# Sheet_1_2022-03-15.net
KiCad netlist of a schematic drawn in Altium Designer
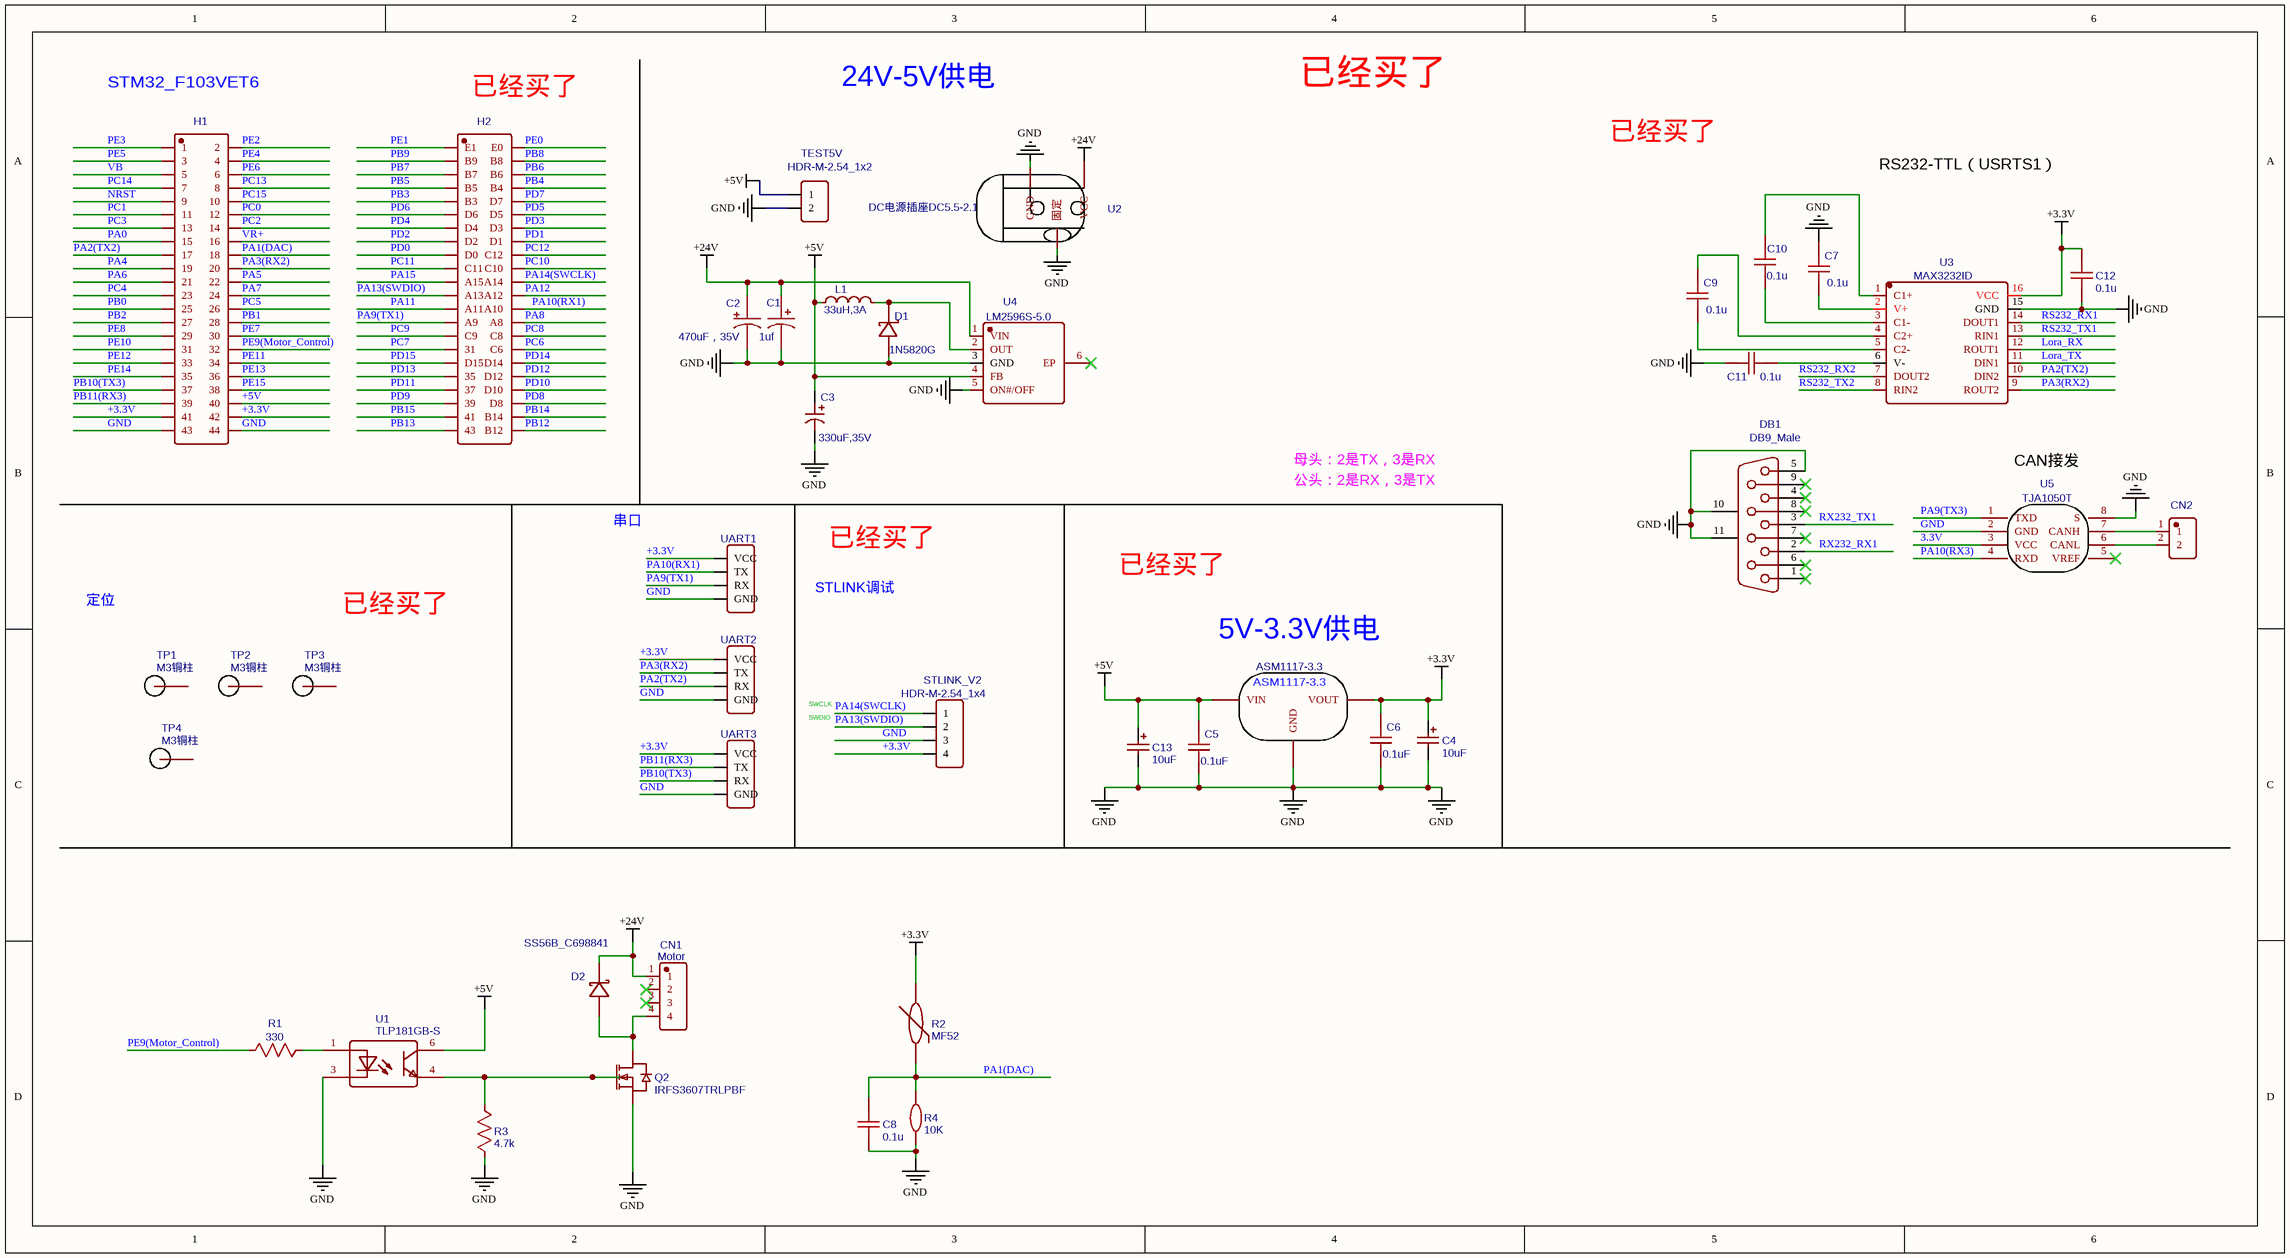
[diagram p0: Sheet_1_2022-03-15.schdoc]

(export (version "E")
  (design (tool "Eeschema 10.0.6"))
  (components
    (comp (ref "5V-3.3V")
      (value "ASM1117-3.3")
      (footprint "ASM1117-5.0-SOT223")
      (fields (field (name "CONTRIBUTOR") "15770626102wlh"))
      (libsource (lib "altium-import") (part "root_0_ASM1117-3.3_"))
    )
    (comp (ref "C1")
      (value "1uf")
      (footprint "CASE-A_3216")
      (fields (field (name "CONTRIBUTOR") "LCEDA_Lib"))
      (libsource (lib "altium-import") (part "root_3_1uf_"))
    )
    (comp (ref "C2")
      (value "470uF，35V")
      (footprint "CAP-SMD_BD10.0-L10.3-W10.3-FD")
      (fields
        (field (name "BOM_SUPPLIER PART") "C125977")
        (field (name "BOM_MANUFACTURER PART") "UWT1H221MNL1GS")
        (field (name "CONTRIBUTOR") "LCSC")
      )
      (libsource (lib "altium-import") (part "root_0_470uF，35V_"))
    )
    (comp (ref "C3")
      (value "330uF,35V")
      (footprint "CAP-SMD_BD10.0-L10.3-W10.3-LS11.0-FD")
      (fields
        (field (name "BOM_SUPPLIER PART") "C2895285")
        (field (name "BOM_MANUFACTURER PART") "RVT330UF35V67RV0163")
        (field (name "CONTRIBUTOR") "LCSC")
      )
      (libsource (lib "altium-import") (part "root_3_330uF,35V_"))
    )
    (comp (ref "C4")
      (value "10uF")
      (footprint "CAP-SMD_L3.2-W1.6-R-RD")
      (fields
        (field (name "BOM_MANUFACTURER PART") "TC212A106K016Y")
        (field (name "BOM_SUPPLIER PART") "C108529")
      )
      (libsource (lib "altium-import") (part "root_1_10uF_"))
    )
    (comp (ref "C5")
      (value "0.1uF")
      (footprint "C0603")
      (fields (field (name "CONTRIBUTOR") "LCEDA_Lib"))
      (libsource (lib "altium-import") (part "root_1_0.1uF_"))
    )
    (comp (ref "C6")
      (value "0.1uF")
      (footprint "C0603")
      (fields (field (name "CONTRIBUTOR") "LCEDA_Lib"))
      (libsource (lib "altium-import") (part "root_1_0.1uF_"))
    )
    (comp (ref "C7")
      (value "0.1u")
      (footprint "C0603")
      (fields (field (name "CONTRIBUTOR") "LCEDA_Lib"))
      (libsource (lib "altium-import") (part "root_1_0.1u_"))
    )
    (comp (ref "C8")
      (value "0.1u")
      (footprint "C0603")
      (fields (field (name "CONTRIBUTOR") "LCEDA_Lib"))
      (libsource (lib "altium-import") (part "root_1_0.1u_"))
    )
    (comp (ref "C9")
      (value "0.1u")
      (footprint "C0603")
      (fields (field (name "CONTRIBUTOR") "LCEDA_Lib"))
      (libsource (lib "altium-import") (part "root_1_0.1u_"))
    )
    (comp (ref "C10")
      (value "0.1u")
      (footprint "C0603")
      (fields (field (name "CONTRIBUTOR") "LCEDA_Lib"))
      (libsource (lib "altium-import") (part "root_1_0.1u_"))
    )
    (comp (ref "C11")
      (value "0.1u")
      (footprint "C0603")
      (fields (field (name "CONTRIBUTOR") "LCEDA_Lib"))
      (libsource (lib "altium-import") (part "root_0_0.1u_"))
    )
    (comp (ref "C12")
      (value "0.1u")
      (footprint "C0603")
      (fields (field (name "CONTRIBUTOR") "LCEDA_Lib"))
      (libsource (lib "altium-import") (part "root_1_0.1u_"))
    )
    (comp (ref "C13")
      (value "10uF")
      (footprint "CAP-SMD_L3.2-W1.6-R-RD")
      (fields
        (field (name "BOM_MANUFACTURER PART") "TC212A106K016Y")
        (field (name "BOM_SUPPLIER PART") "C108529")
      )
      (libsource (lib "altium-import") (part "root_1_10uF_"))
    )
    (comp (ref "CN1")
      (value "Motor")
      (footprint "CONN-TH_4P-P3.81_DB2EVC-3.81-4P")
      (fields
        (field (name "BOM_SUPPLIER PART") "C395697")
        (field (name "BOM_MANUFACTURER PART") "DB2EVC-3.81-4P")
        (field (name "CONTRIBUTOR") "LCSC")
      )
      (libsource (lib "altium-import") (part "root_0_Motor_"))
    )
    (comp (ref "CN2")
      (value "XY2500V-E-3.81-2P")
      (footprint "CONN-TH_XY2500V-E-3.81-2P")
      (fields (field (name "BOM_SUPPLIER PART") "C880563") (field (name "CONTRIBUTOR") "LCSC"))
      (libsource (lib "altium-import") (part "root_0_XY2500V-E-3.81-2P_"))
    )
    (comp (ref "D1")
      (value "1N5820G")
      (footprint "DO-201AD_BD5.3-L8.4-P12.50-D1.4-RD")
      (fields (field (name "BOM_SUPPLIER PART") "C95400") (field (name "CONTRIBUTOR") "LCSC"))
      (libsource (lib "altium-import") (part "root_3_1N5820G_"))
    )
    (comp (ref "D2")
      (value "SS56B_C698841")
      (footprint "SMB_L4.6-W3.6-LS5.3-RD")
      (fields
        (field (name "BOM_SUPPLIER PART") "C698841")
        (field (name "BOM_MANUFACTURER PART") "SS56B")
        (field (name "CONTRIBUTOR") "LCSC")
      )
      (libsource (lib "altium-import") (part "root_3_SS56B_C698841_"))
    )
    (comp (ref "DB1")
      (value "DB9_Male")
      (footprint "DSUB-TH_DMR-9P")
      (fields (field (name "BOM_SUPPLIER PART") "C185657") (field (name "CONTRIBUTOR") "LCEDA_Lib"))
      (libsource (lib "altium-import") (part "root_2_DB9_Male_"))
    )
    (comp (ref "H1")
      (value "X5521FV-2X22C70D30-1000")
      (footprint "HDR-TH_44P-P2.54-V-F-R2-C22-S2.54")
      (fields
        (field (name "BOM_SUPPLIER PART") "C2682209")
        (field (name "BOM_MANUFACTURER PART") "X5521FV-2x22C70D30-1000")
        (field (name "CONTRIBUTOR") "LCSC")
      )
      (libsource (lib "altium-import") (part "root_0_X5521FV-2X22C70D30-1000_"))
    )
    (comp (ref "H2")
      (value "从5")
      (footprint "HDR-TH_44P-P2.54-V-F-R2-C22-S2.54")
      (fields
        (field (name "BOM_SUPPLIER PART") "C2682209")
        (field (name "BOM_MANUFACTURER PART") "X5521FV-2x22C70D30-1000")
        (field (name "CONTRIBUTOR") "LCSC")
      )
      (libsource (lib "altium-import") (part "root_0_从5_"))
    )
    (comp (ref "L1")
      (value "33uH,3A")
      (footprint "IND-SMD_L11.5-W10.0_SMMS1040")
      (fields
        (field (name "BOM_SUPPLIER PART") "C497900")
        (field (name "BOM_MANUFACTURER PART") "YSPI1050-330M")
        (field (name "CONTRIBUTOR") "LCSC")
      )
      (libsource (lib "altium-import") (part "root_0_33uH,3A_"))
    )
    (comp (ref "Q2")
      (value "IRFS3607TRLPBF")
      (footprint "TO-263-2_L10.0-W9.1-P5.08-LS15.2-TL")
      (fields (field (name "BOM_SUPPLIER PART") "C22162"))
      (libsource (lib "altium-import") (part "root_0_IRFS3607TRLPBF_"))
    )
    (comp (ref "R1")
      (value "330")
      (footprint "R0603")
      (fields (field (name "CONTRIBUTOR") "LCEDA_Lib"))
      (libsource (lib "altium-import") (part "root_0_330_"))
    )
    (comp (ref "R2")
      (value "MF52")
      (footprint "RES-TH_L2.5-W2.5-P1.70-D0.3")
      (fields
        (field (name "BOM_MANUFACTURER PART") "MF52A1104F3950(P209-15A)")
        (field (name "BOM_SUPPLIER PART") "C13424")
      )
      (libsource (lib "altium-import") (part "root_1_MF52_"))
    )
    (comp (ref "R3")
      (value "4.7k")
      (footprint "R0805")
      (fields (field (name "CONTRIBUTOR") "LCEDA_Lib"))
      (libsource (lib "altium-import") (part "root_1_4.7k_"))
    )
    (comp (ref "R4")
      (value "10K")
      (footprint "R0805")
      (fields
        (field (name "BOM_SUPPLIER PART") "C188360")
        (field (name "BOM_MANUFACTURER PART") "TR0805B10KP0525")
        (field (name "CONTRIBUTOR") "LCSC")
      )
      (libsource (lib "altium-import") (part "root_1_10K_"))
    )
    (comp (ref "STLINK_V2")
      (value "HDR-M-2.54_1x4")
      (footprint "HDR-M-2.54_1X4")
      (fields (field (name "BOM_SUPPLIER PART") "C124378") (field (name "CONTRIBUTOR") "LCEDA_Lib"))
      (libsource (lib "altium-import") (part "root_0_HDR-M-2.54_1x4_"))
    )
    (comp (ref "TEST5V")
      (value "HDR-M-2.54_1x2")
      (footprint "HDR-M-2.54_1X2")
      (fields (field (name "BOM_SUPPLIER PART") "C124375") (field (name "CONTRIBUTOR") "LCEDA_Lib"))
      (libsource (lib "altium-import") (part "root_0_HDR-M-2.54_1x2_"))
    )
    (comp (ref "TP1")
      (value "M3铜柱")
      (footprint "M3铜柱")
      (fields (field (name "CONTRIBUTOR") "xzxzhao"))
      (libsource (lib "altium-import") (part "root_0_M3铜柱_"))
    )
    (comp (ref "TP2")
      (value "M3铜柱")
      (footprint "M3铜柱")
      (fields (field (name "CONTRIBUTOR") "xzxzhao"))
      (libsource (lib "altium-import") (part "root_0_M3铜柱_"))
    )
    (comp (ref "TP3")
      (value "M3铜柱")
      (footprint "M3铜柱")
      (fields (field (name "CONTRIBUTOR") "xzxzhao"))
      (libsource (lib "altium-import") (part "root_0_M3铜柱_"))
    )
    (comp (ref "TP4")
      (value "M3铜柱")
      (footprint "M3铜柱")
      (fields (field (name "CONTRIBUTOR") "xzxzhao"))
      (libsource (lib "altium-import") (part "root_0_M3铜柱_"))
    )
    (comp (ref "U1")
      (value "TLP181GB-S")
      (footprint "SOP-4_L3.7-W4.6-P2.54-LS7.0-TL")
      (fields (field (name "BOM_SUPPLIER PART") "C388374") (field (name "CONTRIBUTOR") "LCSC"))
      (libsource (lib "altium-import") (part "root_0_TLP181GB-S_"))
    )
    (comp (ref "U2")
      (value "DC电源插座DC5.5-2.1")
      (footprint "DC电源插座5.5-2.1")
      (fields (field (name "CONTRIBUTOR") "Ros智能车"))
      (libsource (lib "altium-import") (part "root_0_DC电源插座DC5.5-2.1_"))
    )
    (comp (ref "U3")
      (value "MAX3232ID")
      (footprint "SOIC-16_L9.9-W3.9-P1.27-LS6.0-BL")
      (fields (field (name "BOM_SUPPLIER PART") "C354119") (field (name "CONTRIBUTOR") "LCSC"))
      (libsource (lib "altium-import") (part "root_0_MAX3232ID_"))
    )
    (comp (ref "U4")
      (value "LM2596S-5.0")
      (footprint "TO-263-5_L10.2-W8.9-P1.70-BR")
      (fields (field (name "BOM_SUPPLIER PART") "C347421") (field (name "CONTRIBUTOR") "LCSC"))
      (libsource (lib "altium-import") (part "root_2_LM2596S-5.0_"))
    )
    (comp (ref "U5")
      (value "TJA1050T")
      (footprint "SOIC-8_L5.0-W4.0-P1.27-LS6.0-BL")
      (fields
        (field (name "BOM_MANUFACTURER PART") "TJA1050T/CM,118")
        (field (name "BOM_SUPPLIER PART") "C6952")
      )
      (libsource (lib "altium-import") (part "root_0_TJA1050T_"))
    )
    (comp (ref "UART1")
      (value "HDR-M-2.54_1x4")
      (footprint "HDR-M-2.54_1X4")
      (fields (field (name "BOM_SUPPLIER PART") "C124378") (field (name "CONTRIBUTOR") "LCEDA_Lib"))
      (libsource (lib "altium-import") (part "root_0_HDR-M-2.54_1x4_"))
    )
    (comp (ref "UART2")
      (value "HDR-M-2.54_1x4")
      (footprint "HDR-M-2.54_1X4")
      (fields (field (name "BOM_SUPPLIER PART") "C124378") (field (name "CONTRIBUTOR") "LCEDA_Lib"))
      (libsource (lib "altium-import") (part "root_0_HDR-M-2.54_1x4_"))
    )
    (comp (ref "UART3")
      (value "HDR-M-2.54_1x4")
      (footprint "HDR-M-2.54_1X4")
      (fields (field (name "BOM_SUPPLIER PART") "C124378") (field (name "CONTRIBUTOR") "LCEDA_Lib"))
      (libsource (lib "altium-import") (part "root_0_HDR-M-2.54_1x4_"))
    )
  )
  (nets
    (net (code "1") (name "+3.3V") (class "Default")
      (node (ref "5V-3.3V") (pin "2") (pinfunction "VOUT_2") (pintype "passive"))
      (node (ref "C12") (pin "2") (pinfunction "2_2") (pintype "passive"))
      (node (ref "C4") (pin "1") (pinfunction "1_1") (pintype "passive"))
      (node (ref "C6") (pin "2") (pinfunction "2_2") (pintype "passive"))
      (node (ref "H1") (pin "41") (pinfunction "41_41") (pintype "passive"))
      (node (ref "H1") (pin "42") (pinfunction "42_42") (pintype "passive"))
      (node (ref "R2") (pin "2") (pinfunction "2_2") (pintype "passive"))
      (node (ref "STLINK_V2") (pin "4") (pinfunction "GND_4") (pintype "passive"))
      (node (ref "U3") (pin "16") (pinfunction "VCC_16") (pintype "passive"))
      (node (ref "UART1") (pin "1") (pinfunction "VCC_1") (pintype "passive"))
      (node (ref "UART2") (pin "1") (pinfunction "VCC_1") (pintype "passive"))
      (node (ref "UART3") (pin "1") (pinfunction "VCC_1") (pintype "passive"))
    )
    (net (code "2") (name "+5V") (class "Default")
      (node (ref "5V-3.3V") (pin "3") (pinfunction "VIN_3") (pintype "passive"))
      (node (ref "C13") (pin "1") (pinfunction "1_1") (pintype "passive"))
      (node (ref "C3") (pin "1") (pinfunction "1_1") (pintype "passive"))
      (node (ref "C5") (pin "2") (pinfunction "2_2") (pintype "passive"))
      (node (ref "H1") (pin "40") (pinfunction "40_40") (pintype "passive"))
      (node (ref "L1") (pin "1") (pinfunction "1_1") (pintype "passive"))
      (node (ref "TEST5V") (pin "1") (pinfunction "1_1") (pintype "passive"))
      (node (ref "U1") (pin "6") (pinfunction "COL_6") (pintype "passive"))
      (node (ref "U4") (pin "4") (pinfunction "FB_4") (pintype "passive"))
    )
    (net (code "3") (name "+24V") (class "Default")
      (node (ref "C1") (pin "1") (pinfunction "1_1") (pintype "passive"))
      (node (ref "C2") (pin "1") (pinfunction "1_1") (pintype "passive"))
      (node (ref "CN1") (pin "1") (pinfunction "1_1") (pintype "passive"))
      (node (ref "D2") (pin "1") (pinfunction "K_1") (pintype "passive"))
      (node (ref "U2") (pin "1") (pinfunction "VCC_1") (pintype "passive"))
      (node (ref "U4") (pin "1") (pinfunction "VIN_1") (pintype "passive"))
    )
    (net (code "4") (name "/3.3V") (class "Default")
      (node (ref "U5") (pin "3") (pinfunction "VCC_3") (pintype "passive"))
    )
    (net (code "5") (name "/Lora_RX") (class "Default")
      (node (ref "U3") (pin "12") (pinfunction "ROUT1_12") (pintype "passive"))
    )
    (net (code "6") (name "/Lora_TX") (class "Default")
      (node (ref "U3") (pin "11") (pinfunction "DIN1_11") (pintype "passive"))
    )
    (net (code "7") (name "/NRST") (class "Default")
      (node (ref "H1") (pin "9") (pinfunction "9_9") (pintype "passive"))
    )
    (net (code "8") (name "/PA0") (class "Default")
      (node (ref "H1") (pin "15") (pinfunction "15_15") (pintype "passive"))
    )
    (net (code "9") (name "/PA1(DAC)") (class "Default")
      (node (ref "C8") (pin "2") (pinfunction "2_2") (pintype "passive"))
      (node (ref "H1") (pin "18") (pinfunction "18_18") (pintype "passive"))
      (node (ref "R2") (pin "1") (pinfunction "1_1") (pintype "passive"))
      (node (ref "R4") (pin "2") (pinfunction "2_2") (pintype "passive"))
    )
    (net (code "10") (name "/PA2(TX2)") (class "Default")
      (node (ref "H1") (pin "17") (pinfunction "17_17") (pintype "passive"))
      (node (ref "U3") (pin "10") (pinfunction "DIN2_10") (pintype "passive"))
      (node (ref "UART2") (pin "3") (pinfunction "RX_3") (pintype "passive"))
    )
    (net (code "11") (name "/PA3(RX2)") (class "Default")
      (node (ref "H1") (pin "20") (pinfunction "20_20") (pintype "passive"))
      (node (ref "U3") (pin "9") (pinfunction "ROUT2_9") (pintype "passive"))
      (node (ref "UART2") (pin "2") (pinfunction "TX_2") (pintype "passive"))
    )
    (net (code "12") (name "/PA4") (class "Default")
      (node (ref "H1") (pin "19") (pinfunction "19_19") (pintype "passive"))
    )
    (net (code "13") (name "/PA5") (class "Default")
      (node (ref "H1") (pin "22") (pinfunction "22_22") (pintype "passive"))
    )
    (net (code "14") (name "/PA6") (class "Default")
      (node (ref "H1") (pin "21") (pinfunction "21_21") (pintype "passive"))
    )
    (net (code "15") (name "/PA7") (class "Default")
      (node (ref "H1") (pin "24") (pinfunction "24_24") (pintype "passive"))
    )
    (net (code "16") (name "/PA8") (class "Default")
      (node (ref "H2") (pin "28") (pinfunction "A8_28") (pintype "passive"))
    )
    (net (code "17") (name "/PA9(TX1)") (class "Default")
      (node (ref "H2") (pin "27") (pinfunction "A9_27") (pintype "passive"))
      (node (ref "UART1") (pin "3") (pinfunction "RX_3") (pintype "passive"))
    )
    (net (code "18") (name "/PA9(TX3)") (class "Default")
      (node (ref "U5") (pin "1") (pinfunction "TXD_1") (pintype "passive"))
    )
    (net (code "19") (name "/PA10(RX1)") (class "Default")
      (node (ref "H2") (pin "26") (pinfunction "A10_26") (pintype "passive"))
      (node (ref "UART1") (pin "2") (pinfunction "TX_2") (pintype "passive"))
    )
    (net (code "20") (name "/PA10(RX3)") (class "Default")
      (node (ref "U5") (pin "4") (pinfunction "RXD_4") (pintype "passive"))
    )
    (net (code "21") (name "/PA11") (class "Default")
      (node (ref "H2") (pin "25") (pinfunction "A11_25") (pintype "passive"))
    )
    (net (code "22") (name "/PA12") (class "Default")
      (node (ref "H2") (pin "24") (pinfunction "A12_24") (pintype "passive"))
    )
    (net (code "23") (name "/PA13(SWDIO)") (class "Default")
      (node (ref "H2") (pin "23") (pinfunction "A13_23") (pintype "passive"))
      (node (ref "STLINK_V2") (pin "2") (pinfunction "TX_2") (pintype "passive"))
    )
    (net (code "24") (name "/PA14(SWCLK)") (class "Default")
      (node (ref "H2") (pin "22") (pinfunction "A14_22") (pintype "passive"))
      (node (ref "STLINK_V2") (pin "1") (pinfunction "VCC_1") (pintype "passive"))
    )
    (net (code "25") (name "/PA15") (class "Default")
      (node (ref "H2") (pin "21") (pinfunction "A15_21") (pintype "passive"))
    )
    (net (code "26") (name "/PB0") (class "Default")
      (node (ref "H1") (pin "25") (pinfunction "25_25") (pintype "passive"))
    )
    (net (code "27") (name "/PB1") (class "Default")
      (node (ref "H1") (pin "28") (pinfunction "28_28") (pintype "passive"))
    )
    (net (code "28") (name "/PB2") (class "Default")
      (node (ref "H1") (pin "27") (pinfunction "27_27") (pintype "passive"))
    )
    (net (code "29") (name "/PB3") (class "Default")
      (node (ref "H2") (pin "9") (pinfunction "B3_9") (pintype "passive"))
    )
    (net (code "30") (name "/PB4") (class "Default")
      (node (ref "H2") (pin "8") (pinfunction "B4_8") (pintype "passive"))
    )
    (net (code "31") (name "/PB5") (class "Default")
      (node (ref "H2") (pin "7") (pinfunction "B5_7") (pintype "passive"))
    )
    (net (code "32") (name "/PB6") (class "Default")
      (node (ref "H2") (pin "6") (pinfunction "B6_6") (pintype "passive"))
    )
    (net (code "33") (name "/PB7") (class "Default")
      (node (ref "H2") (pin "5") (pinfunction "B7_5") (pintype "passive"))
    )
    (net (code "34") (name "/PB8") (class "Default")
      (node (ref "H2") (pin "4") (pinfunction "B8_4") (pintype "passive"))
    )
    (net (code "35") (name "/PB9") (class "Default")
      (node (ref "H2") (pin "3") (pinfunction "B9_3") (pintype "passive"))
    )
    (net (code "36") (name "/PB10(TX3)") (class "Default")
      (node (ref "H1") (pin "37") (pinfunction "37_37") (pintype "passive"))
      (node (ref "UART3") (pin "3") (pinfunction "RX_3") (pintype "passive"))
    )
    (net (code "37") (name "/PB11(RX3)") (class "Default")
      (node (ref "H1") (pin "39") (pinfunction "39_39") (pintype "passive"))
      (node (ref "UART3") (pin "2") (pinfunction "TX_2") (pintype "passive"))
    )
    (net (code "38") (name "/PB12") (class "Default")
      (node (ref "H2") (pin "44") (pinfunction "B12_44") (pintype "passive"))
    )
    (net (code "39") (name "/PB13") (class "Default")
      (node (ref "H2") (pin "43") (pinfunction "43_43") (pintype "passive"))
    )
    (net (code "40") (name "/PB14") (class "Default")
      (node (ref "H2") (pin "42") (pinfunction "B14_42") (pintype "passive"))
    )
    (net (code "41") (name "/PB15") (class "Default")
      (node (ref "H2") (pin "41") (pinfunction "41_41") (pintype "passive"))
    )
    (net (code "42") (name "/PC0") (class "Default")
      (node (ref "H1") (pin "12") (pinfunction "12_12") (pintype "passive"))
    )
    (net (code "43") (name "/PC1") (class "Default")
      (node (ref "H1") (pin "11") (pinfunction "11_11") (pintype "passive"))
    )
    (net (code "44") (name "/PC2") (class "Default")
      (node (ref "H1") (pin "14") (pinfunction "14_14") (pintype "passive"))
    )
    (net (code "45") (name "/PC3") (class "Default")
      (node (ref "H1") (pin "13") (pinfunction "13_13") (pintype "passive"))
    )
    (net (code "46") (name "/PC4") (class "Default")
      (node (ref "H1") (pin "23") (pinfunction "23_23") (pintype "passive"))
    )
    (net (code "47") (name "/PC5") (class "Default")
      (node (ref "H1") (pin "26") (pinfunction "26_26") (pintype "passive"))
    )
    (net (code "48") (name "/PC6") (class "Default")
      (node (ref "H2") (pin "32") (pinfunction "C6_32") (pintype "passive"))
    )
    (net (code "49") (name "/PC7") (class "Default")
      (node (ref "H2") (pin "31") (pinfunction "31_31") (pintype "passive"))
    )
    (net (code "50") (name "/PC8") (class "Default")
      (node (ref "H2") (pin "30") (pinfunction "C8_30") (pintype "passive"))
    )
    (net (code "51") (name "/PC9") (class "Default")
      (node (ref "H2") (pin "29") (pinfunction "C9_29") (pintype "passive"))
    )
    (net (code "52") (name "/PC10") (class "Default")
      (node (ref "H2") (pin "20") (pinfunction "C10_20") (pintype "passive"))
    )
    (net (code "53") (name "/PC11") (class "Default")
      (node (ref "H2") (pin "19") (pinfunction "C11_19") (pintype "passive"))
    )
    (net (code "54") (name "/PC12") (class "Default")
      (node (ref "H2") (pin "18") (pinfunction "C12_18") (pintype "passive"))
    )
    (net (code "55") (name "/PC13") (class "Default")
      (node (ref "H1") (pin "8") (pinfunction "8_8") (pintype "passive"))
    )
    (net (code "56") (name "/PC14") (class "Default")
      (node (ref "H1") (pin "7") (pinfunction "7_7") (pintype "passive"))
    )
    (net (code "57") (name "/PC15") (class "Default")
      (node (ref "H1") (pin "10") (pinfunction "10_10") (pintype "passive"))
    )
    (net (code "58") (name "/PD0") (class "Default")
      (node (ref "H2") (pin "17") (pinfunction "D0_17") (pintype "passive"))
    )
    (net (code "59") (name "/PD1") (class "Default")
      (node (ref "H2") (pin "16") (pinfunction "D1_16") (pintype "passive"))
    )
    (net (code "60") (name "/PD2") (class "Default")
      (node (ref "H2") (pin "15") (pinfunction "D2_15") (pintype "passive"))
    )
    (net (code "61") (name "/PD3") (class "Default")
      (node (ref "H2") (pin "14") (pinfunction "D3_14") (pintype "passive"))
    )
    (net (code "62") (name "/PD4") (class "Default")
      (node (ref "H2") (pin "13") (pinfunction "D4_13") (pintype "passive"))
    )
    (net (code "63") (name "/PD5") (class "Default")
      (node (ref "H2") (pin "12") (pinfunction "D5_12") (pintype "passive"))
    )
    (net (code "64") (name "/PD6") (class "Default")
      (node (ref "H2") (pin "11") (pinfunction "D6_11") (pintype "passive"))
    )
    (net (code "65") (name "/PD7") (class "Default")
      (node (ref "H2") (pin "10") (pinfunction "D7_10") (pintype "passive"))
    )
    (net (code "66") (name "/PD8") (class "Default")
      (node (ref "H2") (pin "40") (pinfunction "D8_40") (pintype "passive"))
    )
    (net (code "67") (name "/PD9") (class "Default")
      (node (ref "H2") (pin "39") (pinfunction "39_39") (pintype "passive"))
    )
    (net (code "68") (name "/PD10") (class "Default")
      (node (ref "H2") (pin "38") (pinfunction "D10_38") (pintype "passive"))
    )
    (net (code "69") (name "/PD11") (class "Default")
      (node (ref "H2") (pin "37") (pinfunction "37_37") (pintype "passive"))
    )
    (net (code "70") (name "/PD12") (class "Default")
      (node (ref "H2") (pin "36") (pinfunction "D12_36") (pintype "passive"))
    )
    (net (code "71") (name "/PD13") (class "Default")
      (node (ref "H2") (pin "35") (pinfunction "35_35") (pintype "passive"))
    )
    (net (code "72") (name "/PD14") (class "Default")
      (node (ref "H2") (pin "34") (pinfunction "D14_34") (pintype "passive"))
    )
    (net (code "73") (name "/PD15") (class "Default")
      (node (ref "H2") (pin "33") (pinfunction "D15_33") (pintype "passive"))
    )
    (net (code "74") (name "/PE0") (class "Default")
      (node (ref "H2") (pin "2") (pinfunction "E0_2") (pintype "passive"))
    )
    (net (code "75") (name "/PE1") (class "Default")
      (node (ref "H2") (pin "1") (pinfunction "E1_1") (pintype "passive"))
    )
    (net (code "76") (name "/PE2") (class "Default")
      (node (ref "H1") (pin "2") (pinfunction "2_2") (pintype "passive"))
    )
    (net (code "77") (name "/PE3") (class "Default")
      (node (ref "H1") (pin "1") (pinfunction "1_1") (pintype "passive"))
    )
    (net (code "78") (name "/PE4") (class "Default")
      (node (ref "H1") (pin "4") (pinfunction "4_4") (pintype "passive"))
    )
    (net (code "79") (name "/PE5") (class "Default")
      (node (ref "H1") (pin "3") (pinfunction "3_3") (pintype "passive"))
    )
    (net (code "80") (name "/PE6") (class "Default")
      (node (ref "H1") (pin "6") (pinfunction "6_6") (pintype "passive"))
    )
    (net (code "81") (name "/PE7") (class "Default")
      (node (ref "H1") (pin "30") (pinfunction "30_30") (pintype "passive"))
    )
    (net (code "82") (name "/PE8") (class "Default")
      (node (ref "H1") (pin "29") (pinfunction "29_29") (pintype "passive"))
    )
    (net (code "83") (name "/PE9(Motor_Control)") (class "Default")
      (node (ref "H1") (pin "32") (pinfunction "32_32") (pintype "passive"))
      (node (ref "R1") (pin "1") (pinfunction "1_1") (pintype "passive"))
    )
    (net (code "84") (name "/PE10") (class "Default")
      (node (ref "H1") (pin "31") (pinfunction "31_31") (pintype "passive"))
    )
    (net (code "85") (name "/PE11") (class "Default")
      (node (ref "H1") (pin "34") (pinfunction "34_34") (pintype "passive"))
    )
    (net (code "86") (name "/PE12") (class "Default")
      (node (ref "H1") (pin "33") (pinfunction "33_33") (pintype "passive"))
    )
    (net (code "87") (name "/PE13") (class "Default")
      (node (ref "H1") (pin "36") (pinfunction "36_36") (pintype "passive"))
    )
    (net (code "88") (name "/PE14") (class "Default")
      (node (ref "H1") (pin "35") (pinfunction "35_35") (pintype "passive"))
    )
    (net (code "89") (name "/PE15") (class "Default")
      (node (ref "H1") (pin "38") (pinfunction "38_38") (pintype "passive"))
    )
    (net (code "90") (name "/RS232_RX1") (class "Default")
      (node (ref "U3") (pin "14") (pinfunction "DOUT1_14") (pintype "passive"))
    )
    (net (code "91") (name "/RS232_RX2") (class "Default")
      (node (ref "U3") (pin "7") (pinfunction "DOUT2_7") (pintype "passive"))
    )
    (net (code "92") (name "/RS232_TX1") (class "Default")
      (node (ref "U3") (pin "13") (pinfunction "RIN1_13") (pintype "passive"))
    )
    (net (code "93") (name "/RS232_TX2") (class "Default")
      (node (ref "U3") (pin "8") (pinfunction "RIN2_8") (pintype "passive"))
    )
    (net (code "94") (name "/RX232_RX1") (class "Default")
      (node (ref "DB1") (pin "2") (pinfunction "2_2") (pintype "passive"))
    )
    (net (code "95") (name "/RX232_TX1") (class "Default")
      (node (ref "DB1") (pin "3") (pinfunction "3_3") (pintype "passive"))
    )
    (net (code "96") (name "/VB") (class "Default")
      (node (ref "H1") (pin "5") (pinfunction "5_5") (pintype "passive"))
    )
    (net (code "97") (name "/VR+") (class "Default")
      (node (ref "H1") (pin "16") (pinfunction "16_16") (pintype "passive"))
    )
    (net (code "98") (name "GND") (class "Default")
      (node (ref "5V-3.3V") (pin "1") (pinfunction "GND_1") (pintype "passive"))
      (node (ref "C1") (pin "2") (pinfunction "2_2") (pintype "passive"))
      (node (ref "C11") (pin "1") (pinfunction "1_1") (pintype "passive"))
      (node (ref "C12") (pin "1") (pinfunction "1_1") (pintype "passive"))
      (node (ref "C13") (pin "2") (pinfunction "2_2") (pintype "passive"))
      (node (ref "C2") (pin "2") (pinfunction "2_2") (pintype "passive"))
      (node (ref "C3") (pin "2") (pinfunction "2_2") (pintype "passive"))
      (node (ref "C4") (pin "2") (pinfunction "2_2") (pintype "passive"))
      (node (ref "C5") (pin "1") (pinfunction "1_1") (pintype "passive"))
      (node (ref "C6") (pin "1") (pinfunction "1_1") (pintype "passive"))
      (node (ref "C7") (pin "2") (pinfunction "2_2") (pintype "passive"))
      (node (ref "C8") (pin "1") (pinfunction "1_1") (pintype "passive"))
      (node (ref "D1") (pin "2") (pinfunction "A_2") (pintype "passive"))
      (node (ref "DB1") (pin "10") (pinfunction "MH1_10") (pintype "passive"))
      (node (ref "DB1") (pin "11") (pinfunction "MH2_11") (pintype "passive"))
      (node (ref "DB1") (pin "5") (pinfunction "5_5") (pintype "passive"))
      (node (ref "H1") (pin "43") (pinfunction "43_43") (pintype "passive"))
      (node (ref "H1") (pin "44") (pinfunction "44_44") (pintype "passive"))
      (node (ref "Q2") (pin "3") (pinfunction "S_3") (pintype "passive"))
      (node (ref "R3") (pin "1") (pinfunction "1_1") (pintype "passive"))
      (node (ref "R4") (pin "1") (pinfunction "1_1") (pintype "passive"))
      (node (ref "STLINK_V2") (pin "3") (pinfunction "RX_3") (pintype "passive"))
      (node (ref "TEST5V") (pin "2") (pinfunction "2_2") (pintype "passive"))
      (node (ref "U1") (pin "3") (pinfunction "CAT_3") (pintype "passive"))
      (node (ref "U2") (pin "2") (pinfunction "GND_2") (pintype "passive"))
      (node (ref "U2") (pin "3") (pinfunction "固定_3") (pintype "passive"))
      (node (ref "U3") (pin "15") (pinfunction "GND_15") (pintype "passive"))
      (node (ref "U4") (pin "3") (pinfunction "GND_3") (pintype "passive"))
      (node (ref "U4") (pin "5") (pinfunction "ON#/OFF_5") (pintype "passive"))
      (node (ref "U5") (pin "2") (pinfunction "GND_2") (pintype "passive"))
      (node (ref "U5") (pin "8") (pinfunction "S_8") (pintype "passive"))
      (node (ref "UART1") (pin "4") (pinfunction "GND_4") (pintype "passive"))
      (node (ref "UART2") (pin "4") (pinfunction "GND_4") (pintype "passive"))
      (node (ref "UART3") (pin "4") (pinfunction "GND_4") (pintype "passive"))
    )
    (net (code "99") (name "Net-(D1-C)") (class "Default")
      (node (ref "D1") (pin "1") (pinfunction "C_1") (pintype "passive"))
      (node (ref "L1") (pin "2") (pinfunction "2_2") (pintype "passive"))
      (node (ref "U4") (pin "2") (pinfunction "OUT_2") (pintype "passive"))
    )
    (net (code "100") (name "Net-(D2-A)") (class "Default")
      (node (ref "CN1") (pin "4") (pinfunction "4_4") (pintype "passive"))
      (node (ref "D2") (pin "2") (pinfunction "A_2") (pintype "passive"))
      (node (ref "Q2") (pin "4") (pinfunction "D_4") (pintype "passive"))
    )
    (net (code "101") (name "Net-(Q2-G)") (class "Default")
      (node (ref "Q2") (pin "1") (pinfunction "G_1") (pintype "passive"))
      (node (ref "R3") (pin "2") (pinfunction "2_2") (pintype "passive"))
      (node (ref "U1") (pin "4") (pinfunction "EMI_4") (pintype "passive"))
    )
    (net (code "102") (name "Net-(U1-AN)") (class "Default")
      (node (ref "R1") (pin "2") (pinfunction "2_2") (pintype "passive"))
      (node (ref "U1") (pin "1") (pinfunction "AN_1") (pintype "passive"))
    )
    (net (code "103") (name "Net-(U3-C1+)") (class "Default")
      (node (ref "C10") (pin "2") (pinfunction "2_2") (pintype "passive"))
      (node (ref "U3") (pin "1") (pinfunction "C1+_1") (pintype "passive"))
    )
    (net (code "104") (name "Net-(U3-C1-)") (class "Default")
      (node (ref "C10") (pin "1") (pinfunction "1_1") (pintype "passive"))
      (node (ref "U3") (pin "3") (pinfunction "C1-_3") (pintype "passive"))
    )
    (net (code "105") (name "Net-(U3-C2+)") (class "Default")
      (node (ref "C9") (pin "2") (pinfunction "2_2") (pintype "passive"))
      (node (ref "U3") (pin "4") (pinfunction "C2+_4") (pintype "passive"))
    )
    (net (code "106") (name "Net-(U3-C2-)") (class "Default")
      (node (ref "C9") (pin "1") (pinfunction "1_1") (pintype "passive"))
      (node (ref "U3") (pin "5") (pinfunction "C2-_5") (pintype "passive"))
    )
    (net (code "107") (name "Net-(U3-V+)") (class "Default")
      (node (ref "C7") (pin "1") (pinfunction "1_1") (pintype "passive"))
      (node (ref "U3") (pin "2") (pinfunction "V+_2") (pintype "passive"))
    )
    (net (code "108") (name "Net-(U3-V-)") (class "Default")
      (node (ref "C11") (pin "2") (pinfunction "2_2") (pintype "passive"))
      (node (ref "U3") (pin "6") (pinfunction "V-_6") (pintype "passive"))
    )
    (net (code "109") (name "Net-(U5-CANH)") (class "Default")
      (node (ref "CN2") (pin "1") (pinfunction "1_1") (pintype "passive"))
      (node (ref "U5") (pin "7") (pinfunction "CANH_7") (pintype "passive"))
    )
    (net (code "110") (name "Net-(U5-CANL)") (class "Default")
      (node (ref "CN2") (pin "2") (pinfunction "2_2") (pintype "passive"))
      (node (ref "U5") (pin "6") (pinfunction "CANL_6") (pintype "passive"))
    )
    (net (code "111") (name "unconnected-(CN1-Pad2)") (class "Default")
      (node (ref "CN1") (pin "2") (pinfunction "2_2") (pintype "passive+no_connect"))
    )
    (net (code "112") (name "unconnected-(CN1-Pad3)") (class "Default")
      (node (ref "CN1") (pin "3") (pinfunction "3_3") (pintype "passive+no_connect"))
    )
    (net (code "113") (name "unconnected-(DB1-Pad1)") (class "Default")
      (node (ref "DB1") (pin "1") (pinfunction "1_1") (pintype "passive+no_connect"))
    )
    (net (code "114") (name "unconnected-(DB1-Pad4)") (class "Default")
      (node (ref "DB1") (pin "4") (pinfunction "4_4") (pintype "passive+no_connect"))
    )
    (net (code "115") (name "unconnected-(DB1-Pad6)") (class "Default")
      (node (ref "DB1") (pin "6") (pinfunction "6_6") (pintype "passive+no_connect"))
    )
    (net (code "116") (name "unconnected-(DB1-Pad7)") (class "Default")
      (node (ref "DB1") (pin "7") (pinfunction "7_7") (pintype "passive+no_connect"))
    )
    (net (code "117") (name "unconnected-(DB1-Pad8)") (class "Default")
      (node (ref "DB1") (pin "8") (pinfunction "8_8") (pintype "passive+no_connect"))
    )
    (net (code "118") (name "unconnected-(DB1-Pad9)") (class "Default")
      (node (ref "DB1") (pin "9") (pinfunction "9_9") (pintype "passive+no_connect"))
    )
    (net (code "119") (name "unconnected-(TP1-M3-Pad1)") (class "Default")
      (node (ref "TP1") (pin "1") (pinfunction "M3_1") (pintype "passive"))
    )
    (net (code "120") (name "unconnected-(TP2-M3-Pad1)") (class "Default")
      (node (ref "TP2") (pin "1") (pinfunction "M3_1") (pintype "passive"))
    )
    (net (code "121") (name "unconnected-(TP3-M3-Pad1)") (class "Default")
      (node (ref "TP3") (pin "1") (pinfunction "M3_1") (pintype "passive"))
    )
    (net (code "122") (name "unconnected-(TP4-M3-Pad1)") (class "Default")
      (node (ref "TP4") (pin "1") (pinfunction "M3_1") (pintype "passive"))
    )
    (net (code "123") (name "unconnected-(U4-EP-Pad6)") (class "Default")
      (node (ref "U4") (pin "6") (pinfunction "EP_6") (pintype "passive+no_connect"))
    )
    (net (code "124") (name "unconnected-(U5-VREF-Pad5)") (class "Default")
      (node (ref "U5") (pin "5") (pinfunction "VREF_5") (pintype "passive+no_connect"))
    )
  )
)
